# Sheet2.net
KiCad netlist of a schematic drawn in Altium Designer
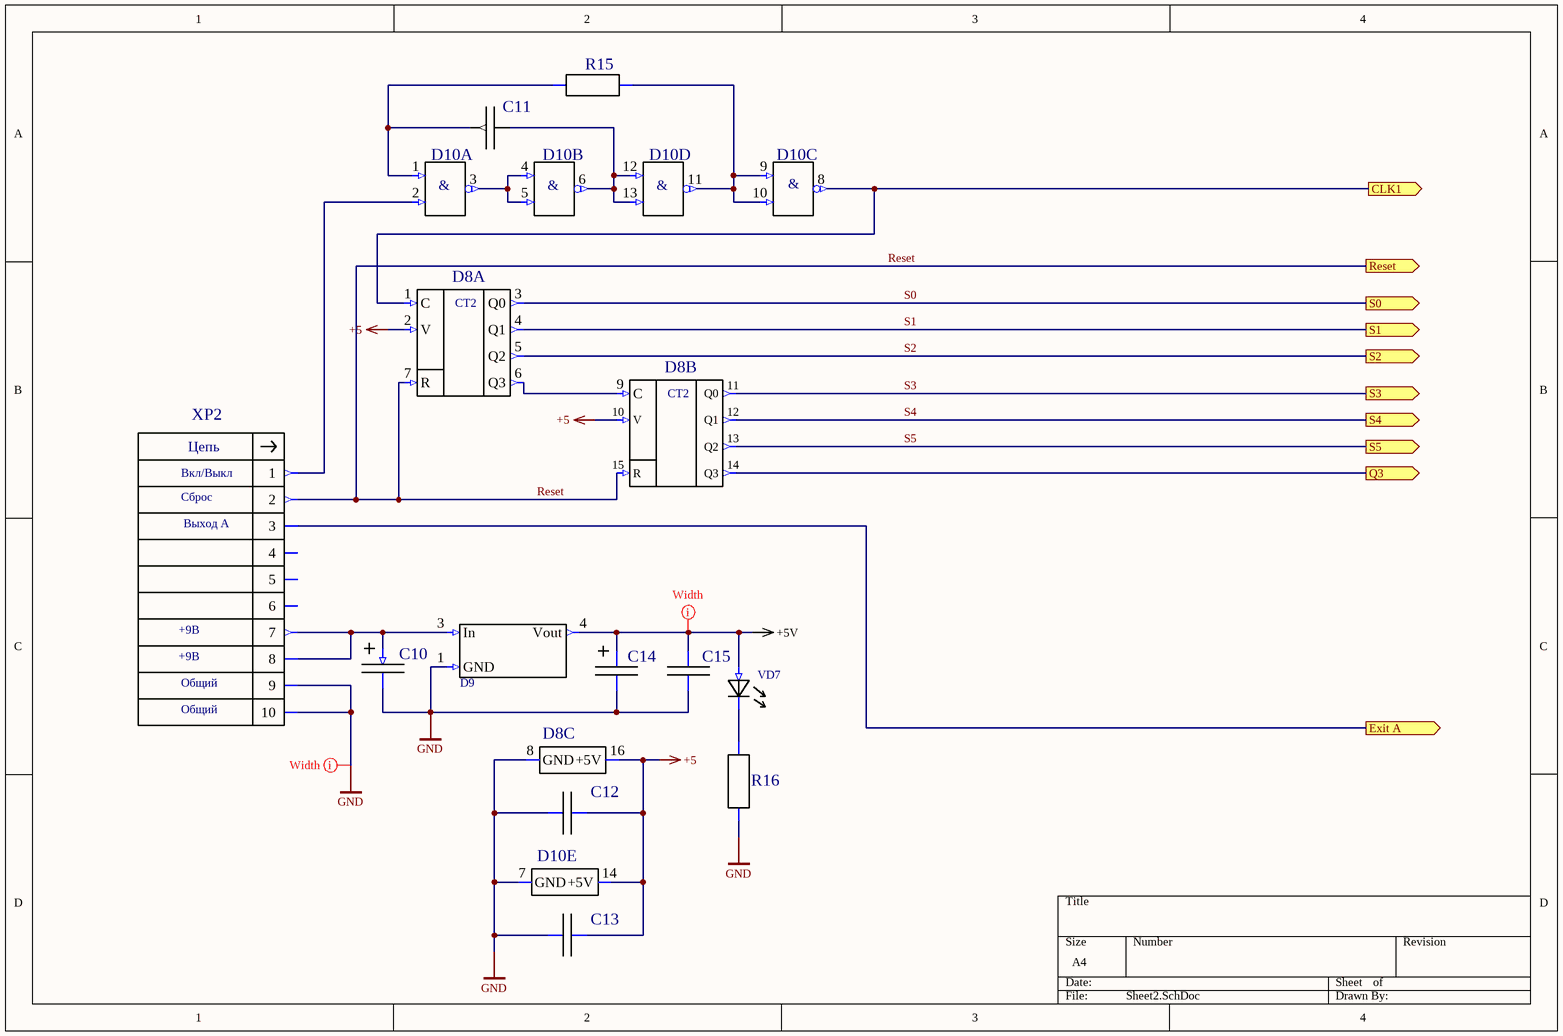
[diagram p0: Sheet2.SchDoc]

(export (version "E")
  (design (tool "Eeschema 10.0.6"))
  (components
    (comp (ref "C10")
      (value "C")
      (footprint "C-Tantal")
      (description "К53-65 Конденсатор танталовый C(6032) 0,47-100 мкФ")
      (fields
        (field (name "VOLTAGE") "16")
        (field (name "MANUFACTURER") "ОАО \"Элеконд\"")
        (field (name "CREATED_BY") "Желобаев")
      )
      (libsource (lib "Int_Library_for_Lessons_3") (part "K53-65_C_10%"))
    )
    (comp (ref "C11")
      (value "1210")
      (footprint "K10-79_3.2_2.5(1210)")
      (description "Чип конденсатор 1210 Н30 ряд Е6")
      (fields (field (name "MANUFACTURER") "ООО \"Кулон\"") (field (name "TOLERANCE") "±20%"))
      (libsource (lib "Int_Library_for_Lessons_3") (part "К10-79_1210_Н30"))
    )
    (comp (ref "C12")
      (value "~")
      (footprint "0805_N")
      (description "Чип конденсатор 0805 Н90 ряд Е6")
      (fields
        (field (name "MANUFACTURER") "ООО \"Кулон\"")
        (field (name "TOLERANCE") "+80%-20%")
        (field (name "CREATED_BY") "Желобаев")
      )
      (libsource (lib "Int_Library_for_Lessons_3") (part "К10-79_0805_Н90"))
    )
    (comp (ref "C13")
      (value "~")
      (footprint "0805_N")
      (description "Чип конденсатор 0805 Н90 ряд Е6")
      (fields
        (field (name "MANUFACTURER") "ООО \"Кулон\"")
        (field (name "TOLERANCE") "+80%-20%")
        (field (name "CREATED_BY") "Желобаев")
      )
      (libsource (lib "Int_Library_for_Lessons_3") (part "К10-79_0805_Н90"))
    )
    (comp (ref "C14")
      (value "C")
      (footprint "C-Tantal")
      (description "К53-65 Конденсатор танталовый C(6032) 0,47-100 мкФ")
      (fields
        (field (name "VOLTAGE") "16")
        (field (name "MANUFACTURER") "ОАО \"Элеконд\"")
        (field (name "CREATED_BY") "Желобаев")
      )
      (libsource (lib "Int_Library_for_Lessons_3") (part "K53-65_C_10%"))
    )
    (comp (ref "C15")
      (value "~")
      (footprint "0805_N")
      (description "Чип конденсатор 0805 Н90 ряд Е6")
      (fields
        (field (name "MANUFACTURER") "ООО \"Кулон\"")
        (field (name "TOLERANCE") "+80%-20%")
        (field (name "CREATED_BY") "Желобаев")
      )
      (libsource (lib "Int_Library_for_Lessons_3") (part "К10-79_0805_Н90"))
    )
    (comp (ref "D8")
      (value "~")
      (footprint "DIP16")
      (description "Два двоичных счетчика")
      (fields (field (name "MANUFACTURER") "Motorola") (field (name "CREATED_BY") "Желобаев"))
      (libsource (lib "Int_Library_for_Lessons_3") (part "MC14520BCP"))
    )
    (comp (ref "D9")
      (value "SOT-223")
      (footprint "LM-1117")
      (description "Преобразователь напряжения 5,0V TO-252")
      (fields (field (name "MANUFACTURER") "\"Texas Instruments\"") (field (name "CREATED_BY") "Шумкин"))
      (libsource (lib "Дополнительные_элементы") (part "LM1117DTX-5,0"))
    )
    (comp (ref "D10")
      (value "74AC00SC")
      (footprint "SO14-N")
      (description "4 элемента 2И-НЕ TTL SOIC-14")
      (fields (field (name "MANUFACTURER") "ON Semiconductor") (field (name "CREATED_BY") "Желобаев"))
      (libsource (lib "Int_Library_for_Lessons_3") (part "74AC00SC"))
    )
    (comp (ref "R15")
      (value "~")
      (footprint "RES_0603_1608_N")
      (description "Резистор от 0,75 Ом до 10 МОм")
      (fields
        (field (name "MANUFACTURER") "ОАО \"НПО \"Эркон\"")
        (field (name "TOLERANCE") "5%")
        (field (name "CREATED_BY") "Желобаев")
      )
      (libsource (lib "Int_Library_for_Lessons_3") (part "Р1-12-0,1-5%"))
    )
    (comp (ref "R16")
      (value "0805")
      (footprint "RES_0805_2012_N")
      (description "Резистор от 0,75 Ом до 2 МОм")
      (fields
        (field (name "MANUFACTURER") "ОАО \"НПО \"Эркон\"")
        (field (name "TOLERANCE") "5%")
        (field (name "CREATED_BY") "Желобаев")
      )
      (libsource (lib "Int_Library_for_Lessons_3") (part "Р1-12-0,125-5%"))
    )
    (comp (ref "VD7")
      (value "521-9466")
      (footprint "521-9466")
      (description "Светодиод жёлтый")
      (fields (field (name "MANUFACTURER") "“Dialight”") (field (name "CREATED_BY") "Шумкин"))
      (libsource (lib "Дополнительные_элементы") (part "521-9466"))
    )
    (comp (ref "XP2")
      (value "TE_1-1634689-0")
      (footprint "BH-10R")
      (description "Вилка типа BH-10R угловая правая двухрядная 2х5х2.54")
      (fields (field (name "MANUFACTURER") "TE Connectivity") (field (name "CREATED_BY") "Желобаев"))
      (libsource (lib "Int_Library_for_Lessons_3") (part "TE_1-1634689-0"))
    )
  )
  (nets
    (net (code "1") (name "+5") (class "Default")
      (node (ref "C12") (pin "2") (pinfunction "2_2") (pintype "passive"))
      (node (ref "C13") (pin "2") (pinfunction "2_2") (pintype "passive"))
      (node (ref "D10") (pin "14") (pinfunction "+5V_14") (pintype "power_in"))
      (node (ref "D8") (pin "10") (pinfunction "V_10") (pintype "input"))
      (node (ref "D8") (pin "16") (pinfunction "+5V_16") (pintype "power_in"))
      (node (ref "D8") (pin "2") (pinfunction "V_2") (pintype "input"))
    )
    (net (code "2") (name "+5V") (class "Default")
      (node (ref "C14") (pin "+") (pinfunction "+_+") (pintype "input"))
      (node (ref "C15") (pin "2") (pinfunction "2_2") (pintype "passive"))
      (node (ref "D9") (pin "4") (pinfunction "Vout_4") (pintype "output"))
      (node (ref "VD7") (pin "A") (pinfunction "A_A") (pintype "input"))
    )
    (net (code "3") (name "/CLK1") (class "Default")
      (node (ref "D10") (pin "8") (pinfunction "Out_8") (pintype "output"))
      (node (ref "D8") (pin "1") (pinfunction "C_1") (pintype "input"))
    )
    (net (code "4") (name "/Exit A") (class "Default")
      (node (ref "XP2") (pin "3") (pinfunction "3_3") (pintype "passive"))
    )
    (net (code "5") (name "/Q3") (class "Default")
      (node (ref "D8") (pin "14") (pinfunction "Q3_14") (pintype "output"))
    )
    (net (code "6") (name "/Reset") (class "Default")
      (node (ref "D8") (pin "15") (pinfunction "R_15") (pintype "input"))
      (node (ref "D8") (pin "7") (pinfunction "R_7") (pintype "input"))
      (node (ref "XP2") (pin "2") (pinfunction "2_2") (pintype "output"))
    )
    (net (code "7") (name "/S0") (class "Default")
      (node (ref "D8") (pin "3") (pinfunction "Q0_3") (pintype "output"))
    )
    (net (code "8") (name "/S1") (class "Default")
      (node (ref "D8") (pin "4") (pinfunction "Q1_4") (pintype "output"))
    )
    (net (code "9") (name "/S2") (class "Default")
      (node (ref "D8") (pin "5") (pinfunction "Q2_5") (pintype "output"))
    )
    (net (code "10") (name "/S3") (class "Default")
      (node (ref "D8") (pin "11") (pinfunction "Q0_11") (pintype "output"))
    )
    (net (code "11") (name "/S4") (class "Default")
      (node (ref "D8") (pin "12") (pinfunction "Q1_12") (pintype "output"))
    )
    (net (code "12") (name "/S5") (class "Default")
      (node (ref "D8") (pin "13") (pinfunction "Q2_13") (pintype "output"))
    )
    (net (code "13") (name "GND") (class "Default")
      (node (ref "C10") (pin "-") (pinfunction "-_-") (pintype "passive"))
      (node (ref "C12") (pin "1") (pinfunction "1_1") (pintype "passive"))
      (node (ref "C13") (pin "1") (pinfunction "1_1") (pintype "passive"))
      (node (ref "C14") (pin "-") (pinfunction "-_-") (pintype "passive"))
      (node (ref "C15") (pin "1") (pinfunction "1_1") (pintype "passive"))
      (node (ref "D10") (pin "7") (pinfunction "GND_7") (pintype "power_in"))
      (node (ref "D8") (pin "8") (pinfunction "GND_8") (pintype "power_in"))
      (node (ref "D9") (pin "1") (pinfunction "GND_1") (pintype "input"))
      (node (ref "R16") (pin "1") (pinfunction "1_1") (pintype "passive"))
      (node (ref "XP2") (pin "10") (pinfunction "10_10") (pintype "passive"))
      (node (ref "XP2") (pin "9") (pinfunction "9_9") (pintype "passive"))
    )
    (net (code "14") (name "Net-(D8A-Q3)") (class "Default")
      (node (ref "D8") (pin "6") (pinfunction "Q3_6") (pintype "output"))
      (node (ref "D8") (pin "9") (pinfunction "C_9") (pintype "input"))
    )
    (net (code "15") (name "Net-(D9-In)") (class "Default")
      (node (ref "C10") (pin "+") (pinfunction "+_+") (pintype "input"))
      (node (ref "D9") (pin "3") (pinfunction "In_3") (pintype "input"))
      (node (ref "XP2") (pin "7") (pinfunction "7_7") (pintype "output"))
      (node (ref "XP2") (pin "8") (pinfunction "8_8") (pintype "passive"))
    )
    (net (code "16") (name "Net-(D10A-In1)") (class "Default")
      (node (ref "C11") (pin "1") (pinfunction "1_1") (pintype "output"))
      (node (ref "D10") (pin "1") (pinfunction "In1_1") (pintype "input"))
      (node (ref "R15") (pin "1") (pinfunction "1_1") (pintype "passive"))
    )
    (net (code "17") (name "Net-(D10A-In2)") (class "Default")
      (node (ref "D10") (pin "2") (pinfunction "In2_2") (pintype "input"))
      (node (ref "XP2") (pin "1") (pinfunction "1_1") (pintype "output"))
    )
    (net (code "18") (name "Net-(D10A-Out)") (class "Default")
      (node (ref "D10") (pin "3") (pinfunction "Out_3") (pintype "output"))
      (node (ref "D10") (pin "4") (pinfunction "In1_4") (pintype "input"))
      (node (ref "D10") (pin "5") (pinfunction "In2_5") (pintype "input"))
    )
    (net (code "19") (name "Net-(D10B-Out)") (class "Default")
      (node (ref "C11") (pin "2") (pinfunction "2_2") (pintype "passive"))
      (node (ref "D10") (pin "12") (pinfunction "In1_12") (pintype "input"))
      (node (ref "D10") (pin "13") (pinfunction "In2_13") (pintype "input"))
      (node (ref "D10") (pin "6") (pinfunction "Out_6") (pintype "output"))
    )
    (net (code "20") (name "Net-(D10C-In1)") (class "Default")
      (node (ref "D10") (pin "10") (pinfunction "In2_10") (pintype "input"))
      (node (ref "D10") (pin "11") (pinfunction "Out_11") (pintype "output"))
      (node (ref "D10") (pin "9") (pinfunction "In1_9") (pintype "input"))
      (node (ref "R15") (pin "2") (pinfunction "2_2") (pintype "passive"))
    )
    (net (code "21") (name "Net-(R16-Pad2)") (class "Default")
      (node (ref "R16") (pin "2") (pinfunction "2_2") (pintype "passive"))
      (node (ref "VD7") (pin "K") (pinfunction "K_K") (pintype "passive"))
    )
    (net (code "22") (name "unconnected-(XP2-Pad4)") (class "Default")
      (node (ref "XP2") (pin "4") (pinfunction "4_4") (pintype "passive"))
    )
    (net (code "23") (name "unconnected-(XP2-Pad5)") (class "Default")
      (node (ref "XP2") (pin "5") (pinfunction "5_5") (pintype "passive"))
    )
    (net (code "24") (name "unconnected-(XP2-Pad6)") (class "Default")
      (node (ref "XP2") (pin "6") (pinfunction "6_6") (pintype "passive"))
    )
  )
)
